# TPS62173_Breakout.net
KiCad netlist of a schematic drawn in EAGLE
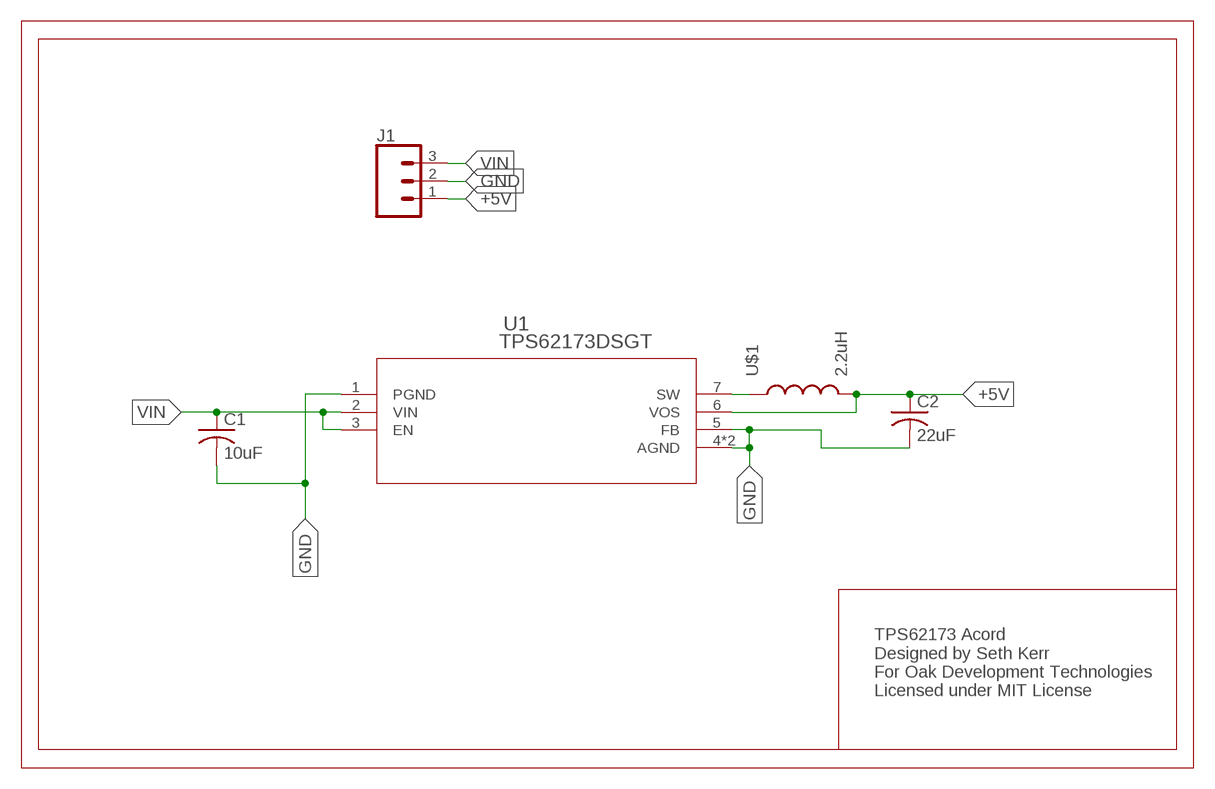
[diagram p0: schematic, sheet 1]

(export (version "E")
  (design (tool "Eeschema 10.0.6"))
  (components
    (comp (ref "C1")
      (value "10uF")
      (footprint "eagle-import:C0603")
      (libsource (lib "eagle-import") (part "C-USC0603"))
    )
    (comp (ref "C2")
      (value "22uF")
      (footprint "eagle-import:C0603")
      (libsource (lib "eagle-import") (part "C-USC0603"))
    )
    (comp (ref "J1")
      (value "CONN_031X03_NO_SILK")
      (footprint "eagle-import:1X03_NO_SILK")
      (libsource (lib "eagle-import") (part "CONN_031X03_NO_SILK"))
    )
    (comp (ref "U$1")
      (value "2.2uH")
      (footprint "eagle-import:2.7X3MM")
      (libsource (lib "eagle-import") (part "NR3015T2R2M"))
    )
    (comp (ref "U1")
      (value "TPS62173DSGT")
      (footprint "eagle-import:DSG8_1P6X0P9_TEX")
      (fields (field (name "MANUFACTURER") "Texas Instruments"))
      (libsource (lib "eagle-import") (part "TPS62173DSGT"))
    )
  )
  (nets
    (net (code "1") (name "+5V") (class "Default")
      (node (ref "C2") (pin "1") (pinfunction "1_1") (pintype "passive"))
      (node (ref "J1") (pin "1") (pinfunction "1_1") (pintype "passive"))
      (node (ref "U$1") (pin "2") (pinfunction "2_2") (pintype "passive"))
      (node (ref "U1") (pin "6") (pinfunction "VOS_6") (pintype "input"))
    )
    (net (code "2") (name "GND") (class "Default")
      (node (ref "C1") (pin "2") (pinfunction "2_2") (pintype "passive"))
      (node (ref "C2") (pin "2") (pinfunction "2_2") (pintype "passive"))
      (node (ref "J1") (pin "2") (pinfunction "2_2") (pintype "passive"))
      (node (ref "U1") (pin "1") (pinfunction "PGND_1") (pintype "power_in"))
      (node (ref "U1") (pin "4") (pinfunction "AGND_4") (pintype "power_in"))
      (node (ref "U1") (pin "5") (pinfunction "FB_5") (pintype "input"))
      (node (ref "U1") (pin "9") (pinfunction "AGND_9") (pintype "power_in"))
    )
    (net (code "3") (name "Net-(U1-SW)") (class "Default")
      (node (ref "U$1") (pin "1") (pinfunction "1_1") (pintype "passive"))
      (node (ref "U1") (pin "7") (pinfunction "SW_7") (pintype "output"))
    )
    (net (code "4") (name "VIN") (class "Default")
      (node (ref "C1") (pin "1") (pinfunction "1_1") (pintype "passive"))
      (node (ref "J1") (pin "3") (pinfunction "3_3") (pintype "passive"))
      (node (ref "U1") (pin "2") (pinfunction "VIN_2") (pintype "input"))
      (node (ref "U1") (pin "3") (pinfunction "EN_3") (pintype "input"))
    )
  )
)
